# SCH_ProMicro_evo2_2025-11-12.net
KiCad netlist of a schematic drawn in EasyEDA
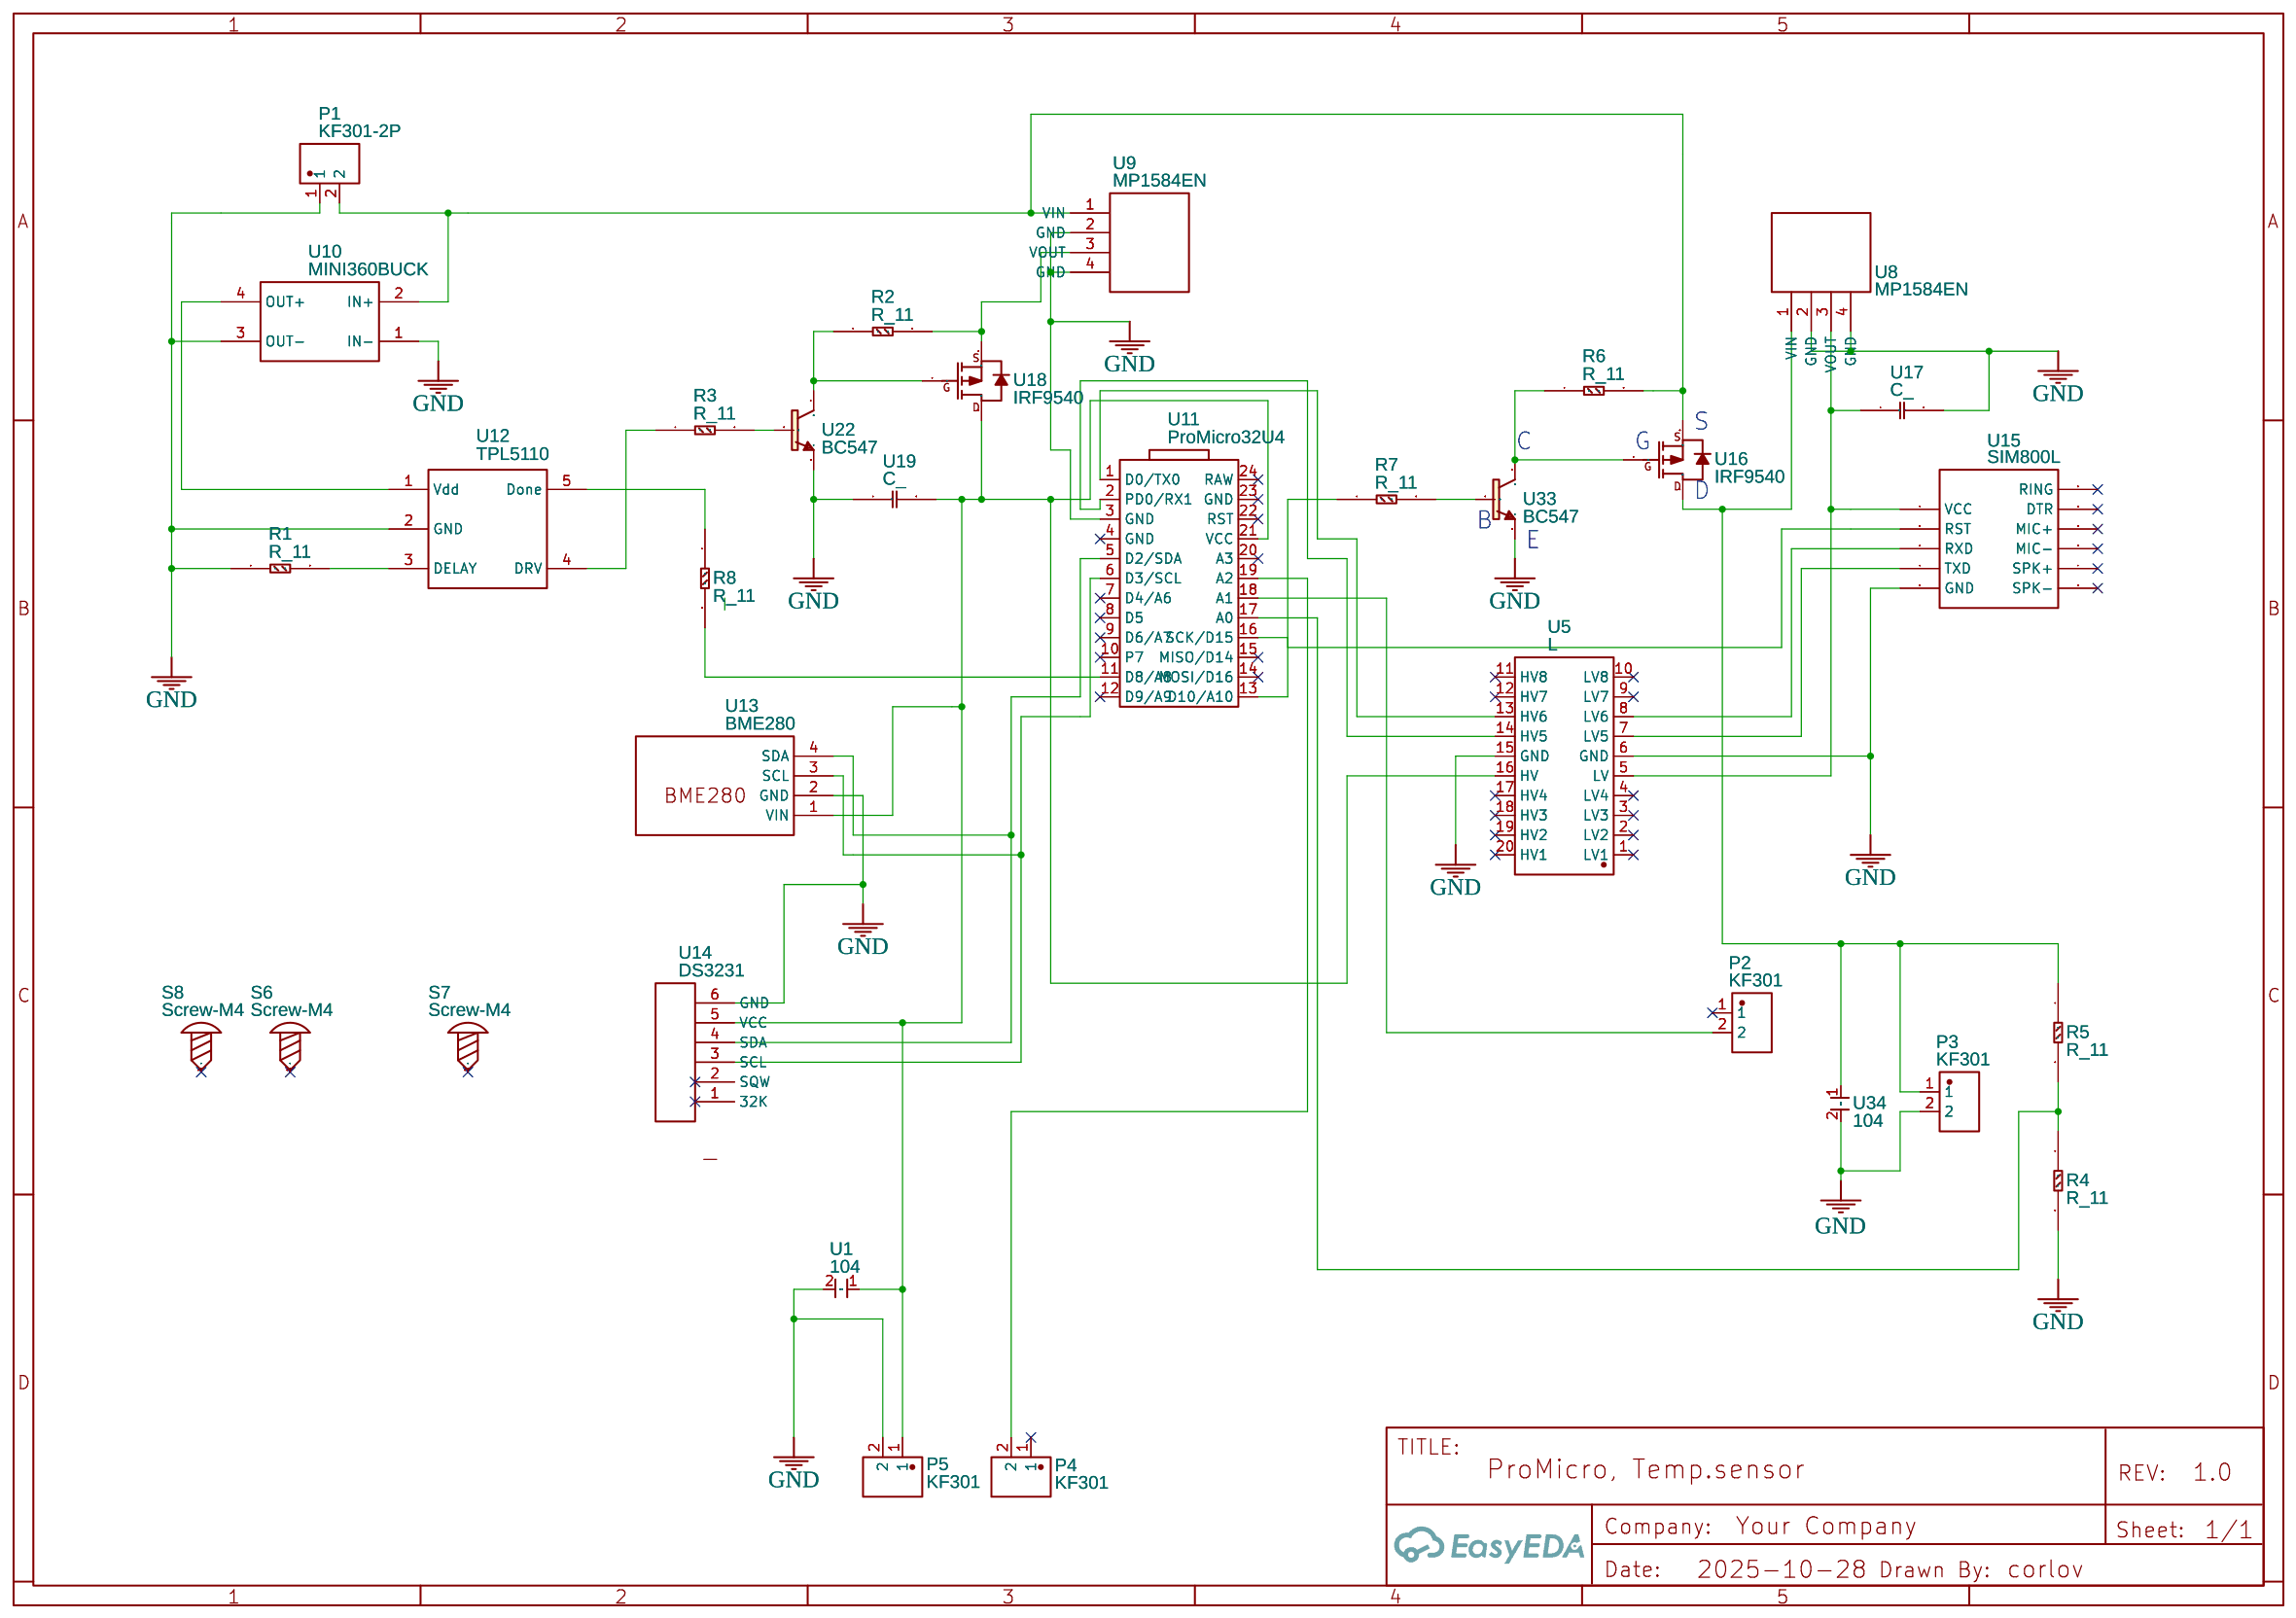
[diagram p0: schematic sheet]

(export (version "E")
  (design (tool "Eeschema 10.0.6"))
  (components
    (comp (ref "P1")
      (value "KF301-2P")
      (fields (field (name "Manufacturer Part") "KF301-2P接线端子"))
      (libsource (lib "") (part "KF301-2P VCC Y GND_2"))
    )
    (comp (ref "P2")
      (value "KF301")
      (fields (field (name "Manufacturer Part") "KF301-2P接线端子"))
      (libsource (lib "") (part "KF301-2P VCC Y GND"))
    )
    (comp (ref "P3")
      (value "KF301")
      (fields (field (name "Manufacturer Part") "KF301-2P接线端子"))
      (libsource (lib "") (part "KF301-2P VCC Y GND"))
    )
    (comp (ref "P4")
      (value "KF301")
      (fields (field (name "Manufacturer Part") "KF301-2P接线端子"))
      (libsource (lib "") (part "KF301-2P VCC Y GND_1"))
    )
    (comp (ref "P5")
      (value "KF301")
      (fields (field (name "Manufacturer Part") "KF301-2P接线端子"))
      (libsource (lib "") (part "KF301-2P VCC Y GND_1"))
    )
    (comp (ref "R1") (value "R_11") (libsource (lib "") (part "R_")))
    (comp (ref "R2") (value "R_11") (libsource (lib "") (part "R_")))
    (comp (ref "R3") (value "R_11") (libsource (lib "") (part "R_")))
    (comp (ref "R4") (value "R_11") (libsource (lib "") (part "R__1")))
    (comp (ref "R5") (value "R_11") (libsource (lib "") (part "R__1")))
    (comp (ref "R6") (value "R_11") (libsource (lib "") (part "R_")))
    (comp (ref "R7") (value "R_11") (libsource (lib "") (part "R_")))
    (comp (ref "R8") (value "R_11") (libsource (lib "") (part "R__1")))
    (comp (ref "S6") (value "Screw-M4") (libsource (lib "") (part "Screw-M4")))
    (comp (ref "S7") (value "Screw-M4") (libsource (lib "") (part "Screw-M4")))
    (comp (ref "S8") (value "Screw-M4") (libsource (lib "") (part "Screw-M4")))
    (comp (ref "U1")
      (value "104")
      (fields (field (name "Manufacturer") "Fe"))
      (libsource (lib "") (part "104_1"))
    )
    (comp (ref "U5")
      (value "L")
      (fields (field (name "Manufacturer Part") "Level Converter 8"))
      (libsource (lib "") (part "LEVEL CONVERTER 8"))
    )
    (comp (ref "U8") (value "MP1584EN") (libsource (lib "") (part "MP1584EN")))
    (comp (ref "U9") (value "MP1584EN") (libsource (lib "") (part "MP1584EN_1")))
    (comp (ref "U10")
      (value "MINI360BUCK")
      (fields (field (name "Manufacturer Part") "Mini360"))
      (libsource (lib "") (part "MINI360BUCK"))
    )
    (comp (ref "U11")
      (value "ProMicro32U4")
      (fields (field (name "Manufacturer Part") "generic"))
      (libsource (lib "") (part "ProMicro32U4"))
    )
    (comp (ref "U12")
      (value "TPL5110")
      (fields (field (name "Manufacturer Part") "3435"))
      (libsource (lib "") (part "ADAFRUIT TPL5110 BREAKOUT"))
    )
    (comp (ref "U13") (value "BME280") (libsource (lib "") (part "BME280")))
    (comp (ref "U14") (value "DS3231") (libsource (lib "") (part "DS3231 upright")))
    (comp (ref "U15") (value "SIM800L") (libsource (lib "") (part "SIM800L")))
    (comp (ref "U16") (value "IRF9540") (libsource (lib "") (part "IRF9540")))
    (comp (ref "U17") (value "C_") (libsource (lib "") (part "C_")))
    (comp (ref "U18") (value "IRF9540") (libsource (lib "") (part "IRF9540")))
    (comp (ref "U19") (value "C_") (libsource (lib "") (part "C_")))
    (comp (ref "U22") (value "BC547") (libsource (lib "") (part "BC547")))
    (comp (ref "U33") (value "BC547") (libsource (lib "") (part "BC547")))
    (comp (ref "U34")
      (value "104")
      (fields (field (name "Manufacturer") "Fe"))
      (libsource (lib "") (part "104"))
    )
  )
  (nets
    (net (code "1") (name "GND") (class "Default")
      (node (ref "P1") (pin "1") (pinfunction "1_1") (pintype "unspecified"))
      (node (ref "P3") (pin "2") (pinfunction "2_2") (pintype "unspecified"))
      (node (ref "P5") (pin "2") (pinfunction "2_2") (pintype "unspecified"))
      (node (ref "R1") (pin "1") (pinfunction "1_1") (pintype "unspecified"))
      (node (ref "R4") (pin "2") (pinfunction "2_2") (pintype "unspecified"))
      (node (ref "U1") (pin "2") (pinfunction "2_2") (pintype "unspecified"))
      (node (ref "U10") (pin "1") (pinfunction "IN-_1") (pintype "unspecified"))
      (node (ref "U10") (pin "3") (pinfunction "OUT-_3") (pintype "unspecified"))
      (node (ref "U11") (pin "3") (pinfunction "GND_3") (pintype "unspecified"))
      (node (ref "U12") (pin "2") (pinfunction "GND_2") (pintype "unspecified"))
      (node (ref "U13") (pin "2") (pinfunction "GND_2") (pintype "unspecified"))
      (node (ref "U14") (pin "6") (pinfunction "GND_6") (pintype "unspecified"))
      (node (ref "U15") (pin "5") (pinfunction "GND_5") (pintype "unspecified"))
      (node (ref "U17") (pin "2") (pinfunction "2_2") (pintype "unspecified"))
      (node (ref "U19") (pin "1") (pinfunction "1_1") (pintype "unspecified"))
      (node (ref "U22") (pin "3") (pinfunction "E_3") (pintype "unspecified"))
      (node (ref "U33") (pin "3") (pinfunction "E_3") (pintype "unspecified"))
      (node (ref "U34") (pin "2") (pinfunction "2_2") (pintype "unspecified"))
      (node (ref "U5") (pin "15") (pinfunction "GND_15") (pintype "unspecified"))
      (node (ref "U5") (pin "6") (pinfunction "GND_6") (pintype "unspecified"))
      (node (ref "U8") (pin "2") (pinfunction "GND_2") (pintype "unspecified"))
      (node (ref "U8") (pin "4") (pinfunction "GND_4") (pintype "unspecified"))
      (node (ref "U9") (pin "2") (pinfunction "GND_2") (pintype "unspecified"))
      (node (ref "U9") (pin "4") (pinfunction "GND_4") (pintype "unspecified"))
    )
    (net (code "2") (name "Net-(U10-IN+)") (class "Default")
      (node (ref "P1") (pin "2") (pinfunction "2_2") (pintype "unspecified"))
      (node (ref "R6") (pin "2") (pinfunction "2_2") (pintype "unspecified"))
      (node (ref "U10") (pin "2") (pinfunction "IN+_2") (pintype "unspecified"))
      (node (ref "U16") (pin "3") (pinfunction "S_3") (pintype "unspecified"))
      (node (ref "U9") (pin "1") (pinfunction "VIN_1") (pintype "unspecified"))
    )
    (net (code "3") (name "Net-(U10-OUT+)") (class "Default")
      (node (ref "U10") (pin "4") (pinfunction "OUT+_4") (pintype "unspecified"))
      (node (ref "U12") (pin "1") (pinfunction "Vdd_1") (pintype "unspecified"))
    )
    (net (code "4") (name "Net-(U11-A0)") (class "Default")
      (node (ref "R4") (pin "1") (pinfunction "1_1") (pintype "unspecified"))
      (node (ref "R5") (pin "2") (pinfunction "2_2") (pintype "unspecified"))
      (node (ref "U11") (pin "17") (pinfunction "A0_17") (pintype "unspecified"))
    )
    (net (code "5") (name "Net-(U11-A1)") (class "Default")
      (node (ref "P2") (pin "2") (pinfunction "2_2") (pintype "unspecified"))
      (node (ref "U11") (pin "18") (pinfunction "A1_18") (pintype "unspecified"))
    )
    (net (code "6") (name "Net-(U11-A2)") (class "Default")
      (node (ref "P4") (pin "2") (pinfunction "2_2") (pintype "unspecified"))
      (node (ref "U11") (pin "19") (pinfunction "A2_19") (pintype "unspecified"))
    )
    (net (code "7") (name "Net-(U11-D0{slash}TX0)") (class "Default")
      (node (ref "U11") (pin "1") (pinfunction "D0/TX0_1") (pintype "unspecified"))
      (node (ref "U5") (pin "13") (pinfunction "HV6_13") (pintype "unspecified"))
    )
    (net (code "8") (name "Net-(U11-D2{slash}SDA)") (class "Default")
      (node (ref "U11") (pin "5") (pinfunction "D2/SDA_5") (pintype "unspecified"))
      (node (ref "U13") (pin "4") (pinfunction "SDA_4") (pintype "unspecified"))
      (node (ref "U14") (pin "4") (pinfunction "SDA_4") (pintype "unspecified"))
    )
    (net (code "9") (name "Net-(U11-D3{slash}SCL)") (class "Default")
      (node (ref "U11") (pin "6") (pinfunction "D3/SCL_6") (pintype "unspecified"))
      (node (ref "U13") (pin "3") (pinfunction "SCL_3") (pintype "unspecified"))
      (node (ref "U14") (pin "3") (pinfunction "SCL_3") (pintype "unspecified"))
    )
    (net (code "10") (name "Net-(U11-D8{slash}A8)") (class "Default")
      (node (ref "R8") (pin "2") (pinfunction "2_2") (pintype "unspecified"))
      (node (ref "U11") (pin "11") (pinfunction "D8/A8_11") (pintype "unspecified"))
    )
    (net (code "11") (name "Net-(U11-D10{slash}A10)") (class "Default")
      (node (ref "R7") (pin "1") (pinfunction "1_1") (pintype "unspecified"))
      (node (ref "U11") (pin "13") (pinfunction "D10/A10_13") (pintype "unspecified"))
    )
    (net (code "12") (name "Net-(U11-PD0{slash}RX1)") (class "Default")
      (node (ref "U11") (pin "2") (pinfunction "PD0/RX1_2") (pintype "unspecified"))
      (node (ref "U5") (pin "14") (pinfunction "HV5_14") (pintype "unspecified"))
    )
    (net (code "13") (name "Net-(U11-SCK{slash}D15)") (class "Default")
      (node (ref "U11") (pin "16") (pinfunction "SCK/D15_16") (pintype "unspecified"))
      (node (ref "U15") (pin "2") (pinfunction "RST_2") (pintype "unspecified"))
    )
    (net (code "14") (name "Net-(U11-VCC)") (class "Default")
      (node (ref "P5") (pin "1") (pinfunction "1_1") (pintype "unspecified"))
      (node (ref "U1") (pin "1") (pinfunction "1_1") (pintype "unspecified"))
      (node (ref "U11") (pin "21") (pinfunction "VCC_21") (pintype "unspecified"))
      (node (ref "U13") (pin "1") (pinfunction "VIN_1") (pintype "unspecified"))
      (node (ref "U14") (pin "5") (pinfunction "VCC_5") (pintype "unspecified"))
      (node (ref "U18") (pin "2") (pinfunction "D_2") (pintype "unspecified"))
      (node (ref "U19") (pin "2") (pinfunction "2_2") (pintype "unspecified"))
      (node (ref "U5") (pin "16") (pinfunction "HV_16") (pintype "unspecified"))
    )
    (net (code "15") (name "Net-(U12-DELAY)") (class "Default")
      (node (ref "R1") (pin "2") (pinfunction "2_2") (pintype "unspecified"))
      (node (ref "U12") (pin "3") (pinfunction "DELAY_3") (pintype "unspecified"))
    )
    (net (code "16") (name "Net-(U12-DRV)") (class "Default")
      (node (ref "R3") (pin "1") (pinfunction "1_1") (pintype "unspecified"))
      (node (ref "U12") (pin "4") (pinfunction "DRV_4") (pintype "unspecified"))
    )
    (net (code "17") (name "Net-(U12-Done)") (class "Default")
      (node (ref "R8") (pin "1") (pinfunction "1_1") (pintype "unspecified"))
      (node (ref "U12") (pin "5") (pinfunction "Done_5") (pintype "unspecified"))
    )
    (net (code "18") (name "Net-(U15-RXD)") (class "Default")
      (node (ref "U15") (pin "3") (pinfunction "RXD_3") (pintype "unspecified"))
      (node (ref "U5") (pin "8") (pinfunction "LV6_8") (pintype "unspecified"))
    )
    (net (code "19") (name "Net-(U15-TXD)") (class "Default")
      (node (ref "U15") (pin "4") (pinfunction "TXD_4") (pintype "unspecified"))
      (node (ref "U5") (pin "7") (pinfunction "LV5_7") (pintype "unspecified"))
    )
    (net (code "20") (name "Net-(U15-VCC)") (class "Default")
      (node (ref "U15") (pin "1") (pinfunction "VCC_1") (pintype "unspecified"))
      (node (ref "U17") (pin "1") (pinfunction "1_1") (pintype "unspecified"))
      (node (ref "U5") (pin "5") (pinfunction "LV_5") (pintype "unspecified"))
      (node (ref "U8") (pin "3") (pinfunction "VOUT_3") (pintype "unspecified"))
    )
    (net (code "21") (name "Net-(U16-D)") (class "Default")
      (node (ref "P3") (pin "1") (pinfunction "1_1") (pintype "unspecified"))
      (node (ref "R5") (pin "1") (pinfunction "1_1") (pintype "unspecified"))
      (node (ref "U16") (pin "2") (pinfunction "D_2") (pintype "unspecified"))
      (node (ref "U34") (pin "1") (pinfunction "1_1") (pintype "unspecified"))
      (node (ref "U8") (pin "1") (pinfunction "VIN_1") (pintype "unspecified"))
    )
    (net (code "22") (name "Net-(U16-G)") (class "Default")
      (node (ref "R6") (pin "1") (pinfunction "1_1") (pintype "unspecified"))
      (node (ref "U16") (pin "1") (pinfunction "G_1") (pintype "unspecified"))
      (node (ref "U33") (pin "1") (pinfunction "C_1") (pintype "unspecified"))
    )
    (net (code "23") (name "Net-(U18-G)") (class "Default")
      (node (ref "R2") (pin "1") (pinfunction "1_1") (pintype "unspecified"))
      (node (ref "U18") (pin "1") (pinfunction "G_1") (pintype "unspecified"))
      (node (ref "U22") (pin "1") (pinfunction "C_1") (pintype "unspecified"))
    )
    (net (code "24") (name "Net-(U18-S)") (class "Default")
      (node (ref "R2") (pin "2") (pinfunction "2_2") (pintype "unspecified"))
      (node (ref "U18") (pin "3") (pinfunction "S_3") (pintype "unspecified"))
      (node (ref "U9") (pin "3") (pinfunction "VOUT_3") (pintype "unspecified"))
    )
    (net (code "25") (name "Net-(U22-B)") (class "Default")
      (node (ref "R3") (pin "2") (pinfunction "2_2") (pintype "unspecified"))
      (node (ref "U22") (pin "2") (pinfunction "B_2") (pintype "unspecified"))
    )
    (net (code "26") (name "Net-(U33-B)") (class "Default")
      (node (ref "R7") (pin "2") (pinfunction "2_2") (pintype "unspecified"))
      (node (ref "U33") (pin "2") (pinfunction "B_2") (pintype "unspecified"))
    )
    (net (code "27") (name "unconnected-(P2-Pad1)") (class "Default")
      (node (ref "P2") (pin "1") (pinfunction "1_1") (pintype "unspecified+no_connect"))
    )
    (net (code "28") (name "unconnected-(P4-Pad1)") (class "Default")
      (node (ref "P4") (pin "1") (pinfunction "1_1") (pintype "unspecified+no_connect"))
    )
    (net (code "29") (name "unconnected-(S6-Pad1)") (class "Default")
      (node (ref "S6") (pin "1") (pinfunction "1_1") (pintype "unspecified+no_connect"))
    )
    (net (code "30") (name "unconnected-(S7-Pad1)") (class "Default")
      (node (ref "S7") (pin "1") (pinfunction "1_1") (pintype "unspecified+no_connect"))
    )
    (net (code "31") (name "unconnected-(S8-Pad1)") (class "Default")
      (node (ref "S8") (pin "1") (pinfunction "1_1") (pintype "unspecified+no_connect"))
    )
    (net (code "32") (name "unconnected-(U5-HV1-Pad20)") (class "Default")
      (node (ref "U5") (pin "20") (pinfunction "HV1_20") (pintype "unspecified+no_connect"))
    )
    (net (code "33") (name "unconnected-(U5-HV2-Pad19)") (class "Default")
      (node (ref "U5") (pin "19") (pinfunction "HV2_19") (pintype "unspecified+no_connect"))
    )
    (net (code "34") (name "unconnected-(U5-HV3-Pad18)") (class "Default")
      (node (ref "U5") (pin "18") (pinfunction "HV3_18") (pintype "unspecified+no_connect"))
    )
    (net (code "35") (name "unconnected-(U5-HV4-Pad17)") (class "Default")
      (node (ref "U5") (pin "17") (pinfunction "HV4_17") (pintype "unspecified+no_connect"))
    )
    (net (code "36") (name "unconnected-(U5-HV7-Pad12)") (class "Default")
      (node (ref "U5") (pin "12") (pinfunction "HV7_12") (pintype "unspecified+no_connect"))
    )
    (net (code "37") (name "unconnected-(U5-HV8-Pad11)") (class "Default")
      (node (ref "U5") (pin "11") (pinfunction "HV8_11") (pintype "unspecified+no_connect"))
    )
    (net (code "38") (name "unconnected-(U5-LV1-Pad1)") (class "Default")
      (node (ref "U5") (pin "1") (pinfunction "LV1_1") (pintype "unspecified+no_connect"))
    )
    (net (code "39") (name "unconnected-(U5-LV2-Pad2)") (class "Default")
      (node (ref "U5") (pin "2") (pinfunction "LV2_2") (pintype "unspecified+no_connect"))
    )
    (net (code "40") (name "unconnected-(U5-LV3-Pad3)") (class "Default")
      (node (ref "U5") (pin "3") (pinfunction "LV3_3") (pintype "unspecified+no_connect"))
    )
    (net (code "41") (name "unconnected-(U5-LV4-Pad4)") (class "Default")
      (node (ref "U5") (pin "4") (pinfunction "LV4_4") (pintype "unspecified+no_connect"))
    )
    (net (code "42") (name "unconnected-(U5-LV7-Pad9)") (class "Default")
      (node (ref "U5") (pin "9") (pinfunction "LV7_9") (pintype "unspecified+no_connect"))
    )
    (net (code "43") (name "unconnected-(U5-LV8-Pad10)") (class "Default")
      (node (ref "U5") (pin "10") (pinfunction "LV8_10") (pintype "unspecified+no_connect"))
    )
    (net (code "44") (name "unconnected-(U11-A3-Pad20)") (class "Default")
      (node (ref "U11") (pin "20") (pinfunction "A3_20") (pintype "unspecified+no_connect"))
    )
    (net (code "45") (name "unconnected-(U11-D4{slash}A6-Pad7)") (class "Default")
      (node (ref "U11") (pin "7") (pinfunction "D4/A6_7") (pintype "unspecified+no_connect"))
    )
    (net (code "46") (name "unconnected-(U11-D5-Pad8)") (class "Default")
      (node (ref "U11") (pin "8") (pinfunction "D5_8") (pintype "unspecified+no_connect"))
    )
    (net (code "47") (name "unconnected-(U11-D6{slash}A7-Pad9)") (class "Default")
      (node (ref "U11") (pin "9") (pinfunction "D6/A7_9") (pintype "unspecified+no_connect"))
    )
    (net (code "48") (name "unconnected-(U11-D9{slash}A9-Pad12)") (class "Default")
      (node (ref "U11") (pin "12") (pinfunction "D9/A9_12") (pintype "unspecified+no_connect"))
    )
    (net (code "49") (name "unconnected-(U11-GND-Pad4)") (class "Default")
      (node (ref "U11") (pin "4") (pinfunction "GND_4") (pintype "unspecified+no_connect"))
    )
    (net (code "50") (name "unconnected-(U11-GND-Pad23)") (class "Default")
      (node (ref "U11") (pin "23") (pinfunction "GND_23") (pintype "unspecified+no_connect"))
    )
    (net (code "51") (name "unconnected-(U11-MISO{slash}D14-Pad15)") (class "Default")
      (node (ref "U11") (pin "15") (pinfunction "MISO/D14_15") (pintype "unspecified+no_connect"))
    )
    (net (code "52") (name "unconnected-(U11-MOSI{slash}D16-Pad14)") (class "Default")
      (node (ref "U11") (pin "14") (pinfunction "MOSI/D16_14") (pintype "unspecified+no_connect"))
    )
    (net (code "53") (name "unconnected-(U11-P7-Pad10)") (class "Default")
      (node (ref "U11") (pin "10") (pinfunction "P7_10") (pintype "unspecified+no_connect"))
    )
    (net (code "54") (name "unconnected-(U11-RAW-Pad24)") (class "Default")
      (node (ref "U11") (pin "24") (pinfunction "RAW_24") (pintype "unspecified+no_connect"))
    )
    (net (code "55") (name "unconnected-(U11-RST-Pad22)") (class "Default")
      (node (ref "U11") (pin "22") (pinfunction "RST_22") (pintype "unspecified+no_connect"))
    )
    (net (code "56") (name "unconnected-(U14-32K-Pad1)") (class "Default")
      (node (ref "U14") (pin "1") (pinfunction "32K_1") (pintype "unspecified+no_connect"))
    )
    (net (code "57") (name "unconnected-(U14-SQW-Pad2)") (class "Default")
      (node (ref "U14") (pin "2") (pinfunction "SQW_2") (pintype "unspecified+no_connect"))
    )
    (net (code "58") (name "unconnected-(U15-DTR-Pad10)") (class "Default")
      (node (ref "U15") (pin "10") (pinfunction "DTR_10") (pintype "unspecified+no_connect"))
    )
    (net (code "59") (name "unconnected-(U15-MIC+-Pad9)") (class "Default")
      (node (ref "U15") (pin "9") (pinfunction "MIC+_9") (pintype "unspecified+no_connect"))
    )
    (net (code "60") (name "unconnected-(U15-MIC--Pad8)") (class "Default")
      (node (ref "U15") (pin "8") (pinfunction "MIC-_8") (pintype "unspecified+no_connect"))
    )
    (net (code "61") (name "unconnected-(U15-RING-Pad11)") (class "Default")
      (node (ref "U15") (pin "11") (pinfunction "RING_11") (pintype "unspecified+no_connect"))
    )
    (net (code "62") (name "unconnected-(U15-SPK+-Pad7)") (class "Default")
      (node (ref "U15") (pin "7") (pinfunction "SPK+_7") (pintype "unspecified+no_connect"))
    )
    (net (code "63") (name "unconnected-(U15-SPK--Pad6)") (class "Default")
      (node (ref "U15") (pin "6") (pinfunction "SPK-_6") (pintype "unspecified+no_connect"))
    )
  )
)
